# LED1.net
KiCad netlist of a schematic drawn in Altium Designer
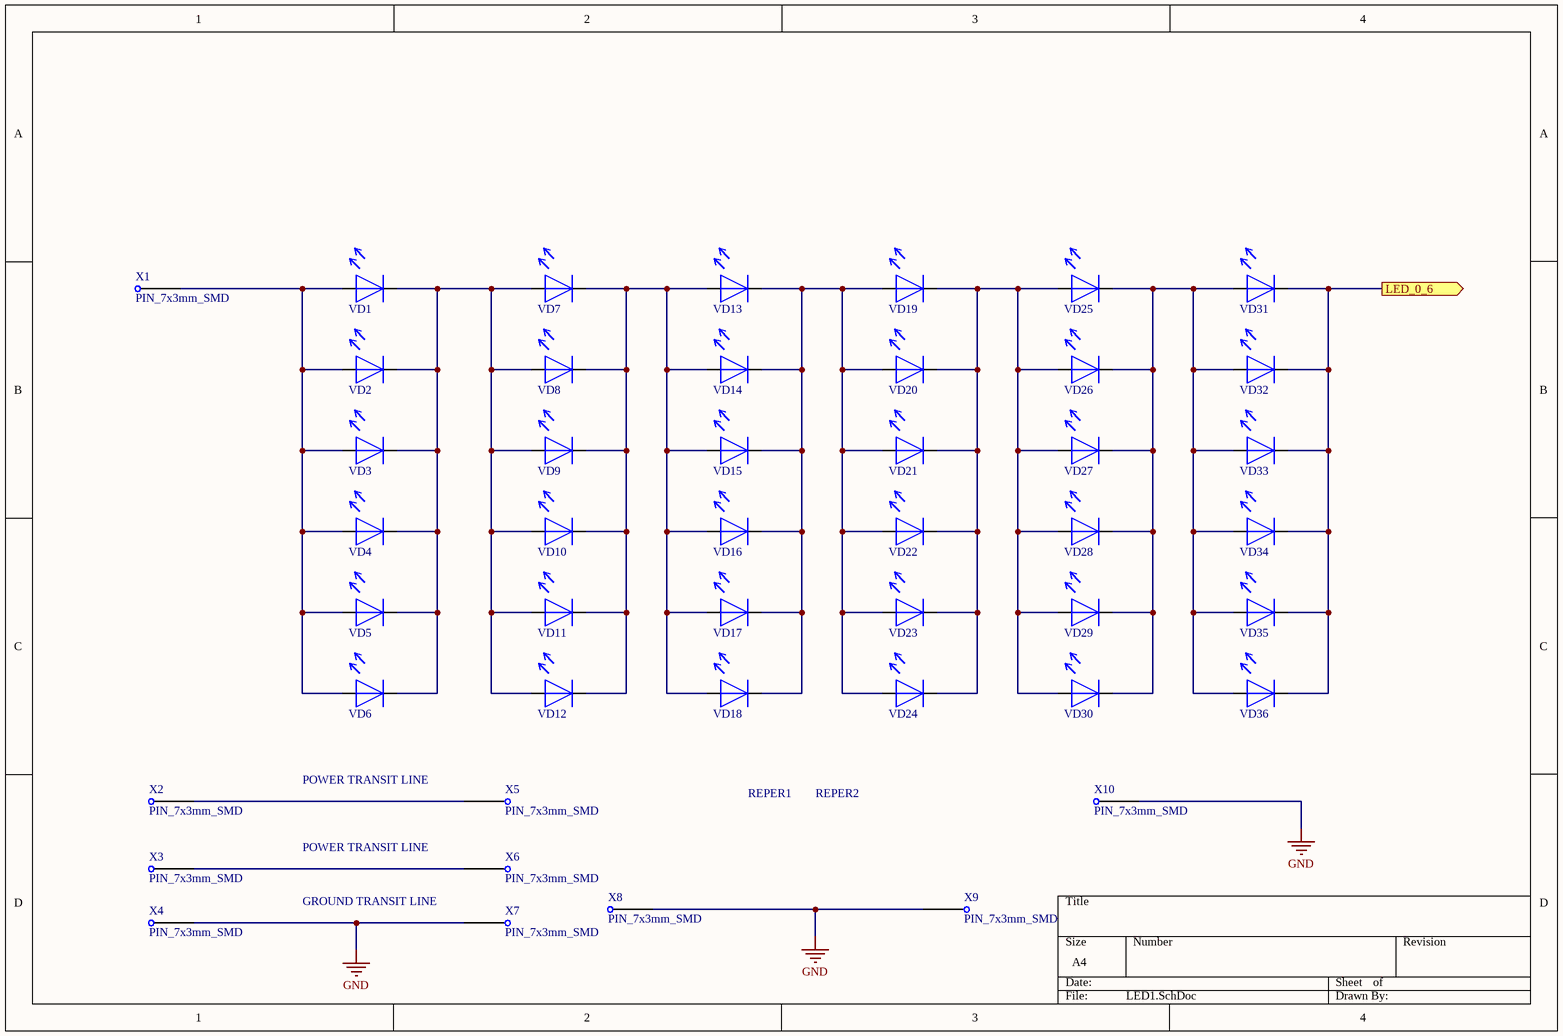
[diagram p0: LED1.SchDoc]

(export (version "E")
  (design (tool "Eeschema 10.0.6"))
  (components
    (comp (ref "1")
      (value "REPER1")
      (footprint "REPER1.2")
      (description "REPER1.2")
      (libsource (lib "gprs_modem_2") (part "REPER1.2"))
    )
    (comp (ref "2")
      (value "REPER2")
      (footprint "REPER1.2")
      (description "REPER1.2")
      (libsource (lib "gprs_modem_2") (part "REPER1.2"))
    )
    (comp (ref "VD1")
      (value "SPMWHT541MD5WAT0SB")
      (footprint "LED_Samsung")
      (libsource (lib "gprs_modem_2") (part "LED SPMWHT541MD5WAT0SB"))
    )
    (comp (ref "VD2")
      (value "SPMWHT541MD5WAT0SB")
      (footprint "LED_Samsung")
      (libsource (lib "gprs_modem_2") (part "LED SPMWHT541MD5WAT0SB"))
    )
    (comp (ref "VD3")
      (value "SPMWHT541MD5WAT0SB")
      (footprint "LED_Samsung")
      (libsource (lib "gprs_modem_2") (part "LED SPMWHT541MD5WAT0SB"))
    )
    (comp (ref "VD4")
      (value "SPMWHT541MD5WAT0SB")
      (footprint "LED_Samsung")
      (libsource (lib "gprs_modem_2") (part "LED SPMWHT541MD5WAT0SB"))
    )
    (comp (ref "VD5")
      (value "SPMWHT541MD5WAT0SB")
      (footprint "LED_Samsung")
      (libsource (lib "gprs_modem_2") (part "LED SPMWHT541MD5WAT0SB"))
    )
    (comp (ref "VD6")
      (value "SPMWHT541MD5WAT0SB")
      (footprint "LED_Samsung")
      (libsource (lib "gprs_modem_2") (part "LED SPMWHT541MD5WAT0SB"))
    )
    (comp (ref "VD7")
      (value "SPMWHT541MD5WAT0SB")
      (footprint "LED_Samsung")
      (libsource (lib "gprs_modem_2") (part "LED SPMWHT541MD5WAT0SB"))
    )
    (comp (ref "VD8")
      (value "SPMWHT541MD5WAT0SB")
      (footprint "LED_Samsung")
      (libsource (lib "gprs_modem_2") (part "LED SPMWHT541MD5WAT0SB"))
    )
    (comp (ref "VD9")
      (value "SPMWHT541MD5WAT0SB")
      (footprint "LED_Samsung")
      (libsource (lib "gprs_modem_2") (part "LED SPMWHT541MD5WAT0SB"))
    )
    (comp (ref "VD10")
      (value "SPMWHT541MD5WAT0SB")
      (footprint "LED_Samsung")
      (libsource (lib "gprs_modem_2") (part "LED SPMWHT541MD5WAT0SB"))
    )
    (comp (ref "VD11")
      (value "SPMWHT541MD5WAT0SB")
      (footprint "LED_Samsung")
      (libsource (lib "gprs_modem_2") (part "LED SPMWHT541MD5WAT0SB"))
    )
    (comp (ref "VD12")
      (value "SPMWHT541MD5WAT0SB")
      (footprint "LED_Samsung")
      (libsource (lib "gprs_modem_2") (part "LED SPMWHT541MD5WAT0SB"))
    )
    (comp (ref "VD13")
      (value "SPMWHT541MD5WAT0SB")
      (footprint "LED_Samsung")
      (libsource (lib "gprs_modem_2") (part "LED SPMWHT541MD5WAT0SB"))
    )
    (comp (ref "VD14")
      (value "SPMWHT541MD5WAT0SB")
      (footprint "LED_Samsung")
      (libsource (lib "gprs_modem_2") (part "LED SPMWHT541MD5WAT0SB"))
    )
    (comp (ref "VD15")
      (value "SPMWHT541MD5WAT0SB")
      (footprint "LED_Samsung")
      (libsource (lib "gprs_modem_2") (part "LED SPMWHT541MD5WAT0SB"))
    )
    (comp (ref "VD16")
      (value "SPMWHT541MD5WAT0SB")
      (footprint "LED_Samsung")
      (libsource (lib "gprs_modem_2") (part "LED SPMWHT541MD5WAT0SB"))
    )
    (comp (ref "VD17")
      (value "SPMWHT541MD5WAT0SB")
      (footprint "LED_Samsung")
      (libsource (lib "gprs_modem_2") (part "LED SPMWHT541MD5WAT0SB"))
    )
    (comp (ref "VD18")
      (value "SPMWHT541MD5WAT0SB")
      (footprint "LED_Samsung")
      (libsource (lib "gprs_modem_2") (part "LED SPMWHT541MD5WAT0SB"))
    )
    (comp (ref "VD19")
      (value "SPMWHT541MD5WAT0SB")
      (footprint "LED_Samsung")
      (libsource (lib "gprs_modem_2") (part "LED SPMWHT541MD5WAT0SB"))
    )
    (comp (ref "VD20")
      (value "SPMWHT541MD5WAT0SB")
      (footprint "LED_Samsung")
      (libsource (lib "gprs_modem_2") (part "LED SPMWHT541MD5WAT0SB"))
    )
    (comp (ref "VD21")
      (value "SPMWHT541MD5WAT0SB")
      (footprint "LED_Samsung")
      (libsource (lib "gprs_modem_2") (part "LED SPMWHT541MD5WAT0SB"))
    )
    (comp (ref "VD22")
      (value "SPMWHT541MD5WAT0SB")
      (footprint "LED_Samsung")
      (libsource (lib "gprs_modem_2") (part "LED SPMWHT541MD5WAT0SB"))
    )
    (comp (ref "VD23")
      (value "SPMWHT541MD5WAT0SB")
      (footprint "LED_Samsung")
      (libsource (lib "gprs_modem_2") (part "LED SPMWHT541MD5WAT0SB"))
    )
    (comp (ref "VD24")
      (value "SPMWHT541MD5WAT0SB")
      (footprint "LED_Samsung")
      (libsource (lib "gprs_modem_2") (part "LED SPMWHT541MD5WAT0SB"))
    )
    (comp (ref "VD25")
      (value "SPMWHT541MD5WAT0SB")
      (footprint "LED_Samsung")
      (libsource (lib "gprs_modem_2") (part "LED SPMWHT541MD5WAT0SB"))
    )
    (comp (ref "VD26")
      (value "SPMWHT541MD5WAT0SB")
      (footprint "LED_Samsung")
      (libsource (lib "gprs_modem_2") (part "LED SPMWHT541MD5WAT0SB"))
    )
    (comp (ref "VD27")
      (value "SPMWHT541MD5WAT0SB")
      (footprint "LED_Samsung")
      (libsource (lib "gprs_modem_2") (part "LED SPMWHT541MD5WAT0SB"))
    )
    (comp (ref "VD28")
      (value "SPMWHT541MD5WAT0SB")
      (footprint "LED_Samsung")
      (libsource (lib "gprs_modem_2") (part "LED SPMWHT541MD5WAT0SB"))
    )
    (comp (ref "VD29")
      (value "SPMWHT541MD5WAT0SB")
      (footprint "LED_Samsung")
      (libsource (lib "gprs_modem_2") (part "LED SPMWHT541MD5WAT0SB"))
    )
    (comp (ref "VD30")
      (value "SPMWHT541MD5WAT0SB")
      (footprint "LED_Samsung")
      (libsource (lib "gprs_modem_2") (part "LED SPMWHT541MD5WAT0SB"))
    )
    (comp (ref "VD31")
      (value "SPMWHT541MD5WAT0SB")
      (footprint "LED_Samsung")
      (libsource (lib "gprs_modem_2") (part "LED SPMWHT541MD5WAT0SB"))
    )
    (comp (ref "VD32")
      (value "SPMWHT541MD5WAT0SB")
      (footprint "LED_Samsung")
      (libsource (lib "gprs_modem_2") (part "LED SPMWHT541MD5WAT0SB"))
    )
    (comp (ref "VD33")
      (value "SPMWHT541MD5WAT0SB")
      (footprint "LED_Samsung")
      (libsource (lib "gprs_modem_2") (part "LED SPMWHT541MD5WAT0SB"))
    )
    (comp (ref "VD34")
      (value "SPMWHT541MD5WAT0SB")
      (footprint "LED_Samsung")
      (libsource (lib "gprs_modem_2") (part "LED SPMWHT541MD5WAT0SB"))
    )
    (comp (ref "VD35")
      (value "SPMWHT541MD5WAT0SB")
      (footprint "LED_Samsung")
      (libsource (lib "gprs_modem_2") (part "LED SPMWHT541MD5WAT0SB"))
    )
    (comp (ref "VD36")
      (value "SPMWHT541MD5WAT0SB")
      (footprint "LED_Samsung")
      (libsource (lib "gprs_modem_2") (part "LED SPMWHT541MD5WAT0SB"))
    )
    (comp (ref "X1")
      (value "PIN_7x3mm_SMD")
      (footprint "PIN_7x3mm_SMD")
      (libsource (lib "gprs_modem") (part "PIN_7x3mm_SMD"))
    )
    (comp (ref "X2")
      (value "PIN_7x3mm_SMD")
      (footprint "PIN_7x3mm_SMD")
      (libsource (lib "gprs_modem") (part "PIN_7x3mm_SMD"))
    )
    (comp (ref "X3")
      (value "PIN_7x3mm_SMD")
      (footprint "PIN_7x3mm_SMD")
      (libsource (lib "gprs_modem") (part "PIN_7x3mm_SMD"))
    )
    (comp (ref "X4")
      (value "PIN_7x3mm_SMD")
      (footprint "PIN_7x3mm_SMD")
      (libsource (lib "gprs_modem") (part "PIN_7x3mm_SMD"))
    )
    (comp (ref "X5")
      (value "PIN_7x3mm_SMD")
      (footprint "PIN_7x3mm_SMD")
      (libsource (lib "gprs_modem") (part "PIN_7x3mm_SMD"))
    )
    (comp (ref "X6")
      (value "PIN_7x3mm_SMD")
      (footprint "PIN_7x3mm_SMD")
      (libsource (lib "gprs_modem") (part "PIN_7x3mm_SMD"))
    )
    (comp (ref "X7")
      (value "PIN_7x3mm_SMD")
      (footprint "PIN_7x3mm_SMD")
      (libsource (lib "gprs_modem") (part "PIN_7x3mm_SMD"))
    )
    (comp (ref "X8")
      (value "PIN_7x3mm_SMD")
      (footprint "PIN_7x3mm_SMD")
      (libsource (lib "gprs_modem") (part "PIN_7x3mm_SMD"))
    )
    (comp (ref "X9")
      (value "PIN_7x3mm_SMD")
      (footprint "PIN_7x3mm_SMD")
      (libsource (lib "gprs_modem") (part "PIN_7x3mm_SMD"))
    )
    (comp (ref "X10")
      (value "PIN_7x3mm_SMD")
      (footprint "PIN_7x3mm_SMD")
      (libsource (lib "gprs_modem") (part "PIN_7x3mm_SMD"))
    )
  )
  (nets
    (net (code "1") (name "/LED_0_6") (class "Default")
      (node (ref "VD31") (pin "2") (pintype "passive"))
      (node (ref "VD32") (pin "2") (pintype "passive"))
      (node (ref "VD33") (pin "2") (pintype "passive"))
      (node (ref "VD34") (pin "2") (pintype "passive"))
      (node (ref "VD35") (pin "2") (pintype "passive"))
      (node (ref "VD36") (pin "2") (pintype "passive"))
    )
    (net (code "2") (name "GND") (class "Default")
      (node (ref "X10") (pin "1") (pinfunction "1_1") (pintype "passive"))
      (node (ref "X4") (pin "1") (pinfunction "1_1") (pintype "passive"))
      (node (ref "X7") (pin "1") (pinfunction "1_1") (pintype "passive"))
      (node (ref "X8") (pin "1") (pinfunction "1_1") (pintype "passive"))
      (node (ref "X9") (pin "1") (pinfunction "1_1") (pintype "passive"))
    )
    (net (code "3") (name "Net-(VD1-Pad1)") (class "Default")
      (node (ref "VD1") (pin "1") (pintype "passive"))
      (node (ref "VD2") (pin "1") (pintype "passive"))
      (node (ref "VD3") (pin "1") (pintype "passive"))
      (node (ref "VD4") (pin "1") (pintype "passive"))
      (node (ref "VD5") (pin "1") (pintype "passive"))
      (node (ref "VD6") (pin "1") (pintype "passive"))
      (node (ref "X1") (pin "1") (pinfunction "1_1") (pintype "passive"))
    )
    (net (code "4") (name "Net-(VD1-Pad2)") (class "Default")
      (node (ref "VD1") (pin "2") (pintype "passive"))
      (node (ref "VD10") (pin "1") (pintype "passive"))
      (node (ref "VD11") (pin "1") (pintype "passive"))
      (node (ref "VD12") (pin "1") (pintype "passive"))
      (node (ref "VD2") (pin "2") (pintype "passive"))
      (node (ref "VD3") (pin "2") (pintype "passive"))
      (node (ref "VD4") (pin "2") (pintype "passive"))
      (node (ref "VD5") (pin "2") (pintype "passive"))
      (node (ref "VD6") (pin "2") (pintype "passive"))
      (node (ref "VD7") (pin "1") (pintype "passive"))
      (node (ref "VD8") (pin "1") (pintype "passive"))
      (node (ref "VD9") (pin "1") (pintype "passive"))
    )
    (net (code "5") (name "Net-(VD10-Pad2)") (class "Default")
      (node (ref "VD10") (pin "2") (pintype "passive"))
      (node (ref "VD11") (pin "2") (pintype "passive"))
      (node (ref "VD12") (pin "2") (pintype "passive"))
      (node (ref "VD13") (pin "1") (pintype "passive"))
      (node (ref "VD14") (pin "1") (pintype "passive"))
      (node (ref "VD15") (pin "1") (pintype "passive"))
      (node (ref "VD16") (pin "1") (pintype "passive"))
      (node (ref "VD17") (pin "1") (pintype "passive"))
      (node (ref "VD18") (pin "1") (pintype "passive"))
      (node (ref "VD7") (pin "2") (pintype "passive"))
      (node (ref "VD8") (pin "2") (pintype "passive"))
      (node (ref "VD9") (pin "2") (pintype "passive"))
    )
    (net (code "6") (name "Net-(VD13-Pad2)") (class "Default")
      (node (ref "VD13") (pin "2") (pintype "passive"))
      (node (ref "VD14") (pin "2") (pintype "passive"))
      (node (ref "VD15") (pin "2") (pintype "passive"))
      (node (ref "VD16") (pin "2") (pintype "passive"))
      (node (ref "VD17") (pin "2") (pintype "passive"))
      (node (ref "VD18") (pin "2") (pintype "passive"))
      (node (ref "VD19") (pin "1") (pintype "passive"))
      (node (ref "VD20") (pin "1") (pintype "passive"))
      (node (ref "VD21") (pin "1") (pintype "passive"))
      (node (ref "VD22") (pin "1") (pintype "passive"))
      (node (ref "VD23") (pin "1") (pintype "passive"))
      (node (ref "VD24") (pin "1") (pintype "passive"))
    )
    (net (code "7") (name "Net-(VD19-Pad2)") (class "Default")
      (node (ref "VD19") (pin "2") (pintype "passive"))
      (node (ref "VD20") (pin "2") (pintype "passive"))
      (node (ref "VD21") (pin "2") (pintype "passive"))
      (node (ref "VD22") (pin "2") (pintype "passive"))
      (node (ref "VD23") (pin "2") (pintype "passive"))
      (node (ref "VD24") (pin "2") (pintype "passive"))
      (node (ref "VD25") (pin "1") (pintype "passive"))
      (node (ref "VD26") (pin "1") (pintype "passive"))
      (node (ref "VD27") (pin "1") (pintype "passive"))
      (node (ref "VD28") (pin "1") (pintype "passive"))
      (node (ref "VD29") (pin "1") (pintype "passive"))
      (node (ref "VD30") (pin "1") (pintype "passive"))
    )
    (net (code "8") (name "Net-(VD25-Pad2)") (class "Default")
      (node (ref "VD25") (pin "2") (pintype "passive"))
      (node (ref "VD26") (pin "2") (pintype "passive"))
      (node (ref "VD27") (pin "2") (pintype "passive"))
      (node (ref "VD28") (pin "2") (pintype "passive"))
      (node (ref "VD29") (pin "2") (pintype "passive"))
      (node (ref "VD30") (pin "2") (pintype "passive"))
      (node (ref "VD31") (pin "1") (pintype "passive"))
      (node (ref "VD32") (pin "1") (pintype "passive"))
      (node (ref "VD33") (pin "1") (pintype "passive"))
      (node (ref "VD34") (pin "1") (pintype "passive"))
      (node (ref "VD35") (pin "1") (pintype "passive"))
      (node (ref "VD36") (pin "1") (pintype "passive"))
    )
    (net (code "9") (name "Net-(X2-Pad1)") (class "Default")
      (node (ref "X2") (pin "1") (pinfunction "1_1") (pintype "passive"))
      (node (ref "X5") (pin "1") (pinfunction "1_1") (pintype "passive"))
    )
    (net (code "10") (name "Net-(X3-Pad1)") (class "Default")
      (node (ref "X3") (pin "1") (pinfunction "1_1") (pintype "passive"))
      (node (ref "X6") (pin "1") (pinfunction "1_1") (pintype "passive"))
    )
    (net (code "11") (name "unconnected-(1-Pad1)") (class "Default")
      (node (ref "1") (pin "1") (pintype "passive"))
    )
    (net (code "12") (name "unconnected-(2-Pad1)") (class "Default")
      (node (ref "2") (pin "1") (pintype "passive"))
    )
  )
)
